# Motors.net
KiCad netlist of a schematic drawn in Altium Designer
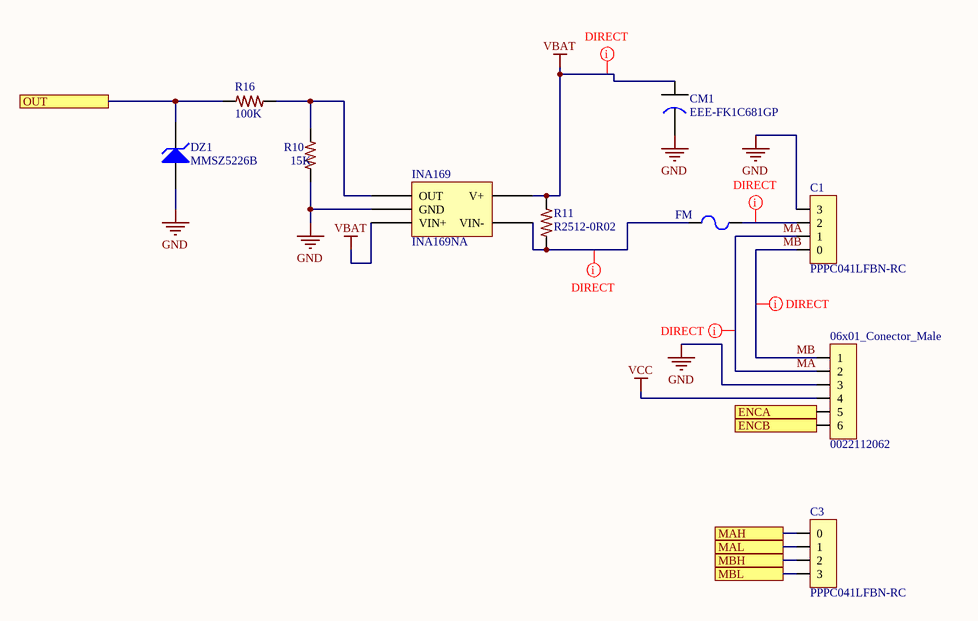
[diagram p0: Motors.SchDoc]

(export (version "E")
  (design (tool "Eeschema 10.0.6"))
  (components
    (comp (ref "06x01_Conector_Male")
      (value "0022112062")
      (footprint "06x01_Conector_Male")
      (description "CONN HEADER 6POS .100 VERT GOLD")
      (libsource (lib "Schlib1") (part "06x01_Conector_Male"))
    )
    (comp (ref "C1")
      (value "PPPC041LFBN-RC")
      (footprint "04x01_Conector_Female")
      (description "4 Position Header Connector 0.100\" (2.54mm) Through Hole Gold")
      (libsource (lib "") (part "04x01_Conector_Female-SCH_1"))
    )
    (comp (ref "C3")
      (value "PPPC041LFBN-RC")
      (footprint "04x01_Conector_Female")
      (description "4 Position Header Connector 0.100\" (2.54mm) Through Hole Gold")
      (libsource (lib "Schlib1") (part "04x01_Conector_Female-SCH"))
    )
    (comp (ref "CM1")
      (value "EEE-FK1C681GP")
      (footprint "EEE-FK1C681GP")
      (description "Aluminum Electrolytic Capacitors - SMD Al Lytic Cap SMT FK Series 105C")
      (libsource (lib "Schlib1") (part "CAP AL 680UF/16V"))
    )
    (comp (ref "DZ1")
      (value "MMSZ5226B")
      (footprint "FAIR-SOD-123-2_V")
      (description "Zener Diode, 3.3 V, -55 to 150 degC, 2-Pin SOD-123，RoHS, Tape and Reel")
      (fields (field (name "MANUFACTURER") "FairchildSemiconductor"))
      (libsource (lib "Altium Content Vault") (part "DZEN-AK-2"))
    )
    (comp (ref "FM")
      (value "MF-MSMF250/16X")
      (footprint "RESC4632X16N")
      (description "PTC RESETTABLE .30A 30V 1812")
      (libsource (lib "IMBEL") (part "MF-MSMF250/16X-01.A.1"))
    )
    (comp (ref "INA169")
      (value "INA169NA")
      (footprint "SOT95P280X125-5N")
      (description "IC CURRENT MONITOR 0.5% SOT23-5")
      (libsource (lib "IMBEL") (part "ina169"))
    )
    (comp (ref "R10")
      (value "15K")
      (footprint "0402-RES-HD")
      (description "RES 1K OHM 1/10W 1% 0402 SMD")
      (fields (field (name "PART NO") "ERJ-2RKF1001X"))
      (libsource (lib "IMBEL") (part "RESISTOR"))
    )
    (comp (ref "R11")
      (value "R2512-0R02")
      (footprint "2512-RES-HD")
      (description "RES .02 OHM 2W 1% 2512 SMD")
      (fields (field (name "PART NO") "WSL2512R0200FEA18"))
      (libsource (lib "IMBEL") (part "R2512-0R02-4"))
    )
    (comp (ref "R16")
      (value "100K")
      (footprint "0402-RES-HD")
      (description "RES 1K OHM 1/10W 1% 0402 SMD")
      (fields (field (name "PART NO") "ERJ-2RKF1001X"))
      (libsource (lib "IMBEL") (part "RESISTOR"))
    )
  )
  (nets
    (net (code "1") (name "/ENCA") (class "Default")
      (node (ref "06x01_Conector_Male") (pin "5") (pinfunction "5_5") (pintype "passive"))
    )
    (net (code "2") (name "/ENCB") (class "Default")
      (node (ref "06x01_Conector_Male") (pin "6") (pinfunction "6_6") (pintype "passive"))
    )
    (net (code "3") (name "/MA") (class "Default")
      (node (ref "06x01_Conector_Male") (pin "2") (pinfunction "2_2") (pintype "passive"))
      (node (ref "C1") (pin "1") (pinfunction "1_1") (pintype "passive"))
    )
    (net (code "4") (name "/MAH") (class "Default")
      (node (ref "C3") (pin "0") (pinfunction "0_0") (pintype "passive"))
    )
    (net (code "5") (name "/MAL") (class "Default")
      (node (ref "C3") (pin "1") (pinfunction "1_1") (pintype "passive"))
    )
    (net (code "6") (name "/MB") (class "Default")
      (node (ref "06x01_Conector_Male") (pin "1") (pinfunction "1_1") (pintype "passive"))
      (node (ref "C1") (pin "0") (pinfunction "0_0") (pintype "passive"))
    )
    (net (code "7") (name "/MBH") (class "Default")
      (node (ref "C3") (pin "2") (pinfunction "2_2") (pintype "passive"))
    )
    (net (code "8") (name "/MBL") (class "Default")
      (node (ref "C3") (pin "3") (pinfunction "3_3") (pintype "passive"))
    )
    (net (code "9") (name "/OUT") (class "Default")
      (node (ref "DZ1") (pin "2") (pinfunction "K_2") (pintype "passive"))
      (node (ref "R16") (pin "2") (pinfunction "2_2") (pintype "passive"))
    )
    (net (code "10") (name "GND") (class "Default")
      (node (ref "06x01_Conector_Male") (pin "3") (pinfunction "3_3") (pintype "passive"))
      (node (ref "C1") (pin "3") (pinfunction "3_3") (pintype "passive"))
      (node (ref "CM1") (pin "2") (pinfunction "2_2") (pintype "passive"))
      (node (ref "DZ1") (pin "1") (pinfunction "A_1") (pintype "passive"))
      (node (ref "INA169") (pin "2") (pinfunction "GND_2") (pintype "passive"))
      (node (ref "R10") (pin "1") (pinfunction "1_1") (pintype "passive"))
    )
    (net (code "11") (name "Net-(C1-Pad2)") (class "Default")
      (node (ref "C1") (pin "2") (pinfunction "2_2") (pintype "passive"))
      (node (ref "FM") (pin "1") (pinfunction "1_1") (pintype "passive"))
    )
    (net (code "12") (name "Net-(INA169-OUT)") (class "Default")
      (node (ref "INA169") (pin "1") (pinfunction "OUT_1") (pintype "passive"))
      (node (ref "R10") (pin "2") (pinfunction "2_2") (pintype "passive"))
      (node (ref "R16") (pin "1") (pinfunction "1_1") (pintype "passive"))
    )
    (net (code "13") (name "Net-(INA169-VIN-)") (class "Default")
      (node (ref "FM") (pin "2") (pinfunction "2_2") (pintype "passive"))
      (node (ref "INA169") (pin "5") (pinfunction "VIN-_5") (pintype "passive"))
      (node (ref "R11") (pin "1") (pinfunction "1_1") (pintype "passive"))
    )
    (net (code "14") (name "VBAT") (class "Default")
      (node (ref "CM1") (pin "1") (pinfunction "1_1") (pintype "passive"))
      (node (ref "INA169") (pin "3") (pinfunction "VIN+_3") (pintype "passive"))
      (node (ref "INA169") (pin "4") (pinfunction "V+_4") (pintype "passive"))
      (node (ref "R11") (pin "2") (pinfunction "2_2") (pintype "passive"))
    )
    (net (code "15") (name "VCC") (class "Default")
      (node (ref "06x01_Conector_Male") (pin "4") (pinfunction "4_4") (pintype "passive"))
    )
  )
)
